# bitsyled-v1_2_1.net
KiCad netlist of a schematic drawn in EAGLE
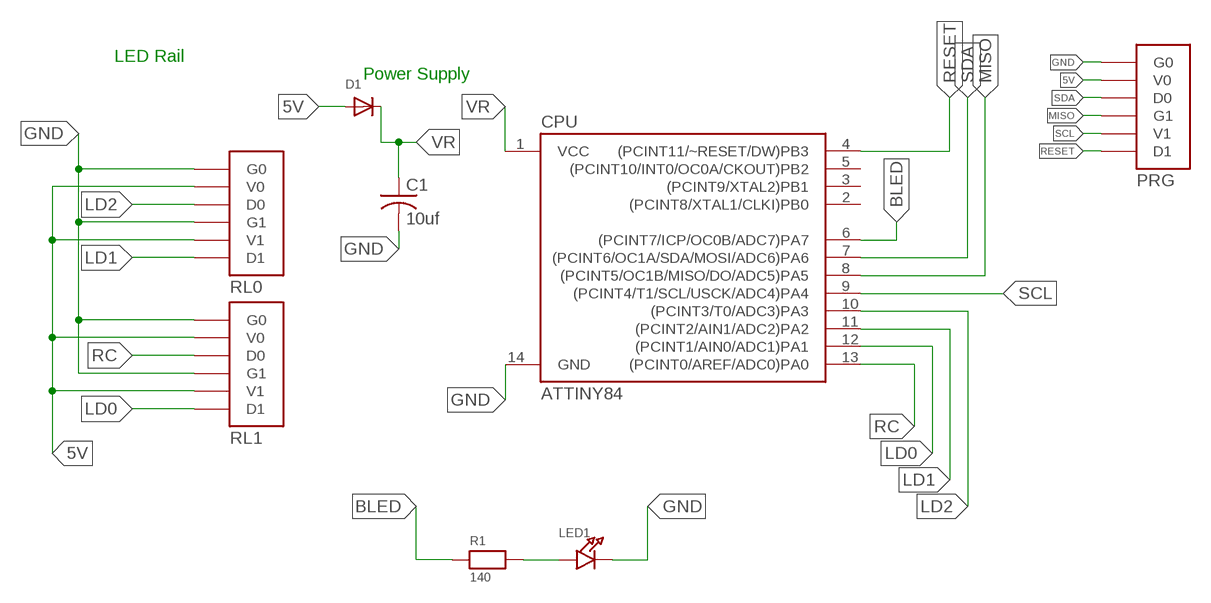
[diagram p0: schematic, sheet 1]

(export (version "E")
  (design (tool "Eeschema 10.0.6"))
  (components
    (comp (ref "C1")
      (value "10uf")
      (footprint "eagle-import:C0805")
      (libsource (lib "eagle-import") (part "C-USC0805"))
    )
    (comp (ref "CPU")
      (value "ATTINY84")
      (footprint "eagle-import:SO14")
      (libsource (lib "eagle-import") (part "ATTINY84"))
    )
    (comp (ref "D1")
      (value "DIODESOD-123")
      (footprint "eagle-import:SOD-123")
      (libsource (lib "eagle-import") (part "DIODESOD-123"))
    )
    (comp (ref "LED1")
      (value "LED0805_NOOUTLINE")
      (footprint "eagle-import:CHIPLED_0805_NOOUTLINE")
      (libsource (lib "eagle-import") (part "LED0805_NOOUTLINE"))
    )
    (comp (ref "PRG")
      (value "BITSYLED_1X6_RAILPRG")
      (footprint "eagle-import:BITSYLED_1X6_RAIL_PRG")
      (libsource (lib "eagle-import") (part "BITSYLED_1X6_RAILPRG"))
    )
    (comp (ref "R1")
      (value "140")
      (footprint "eagle-import:_0805")
      (libsource (lib "eagle-import") (part "RESISTOR_0805"))
    )
    (comp (ref "RL0")
      (value "BITSYLED_1X6_RAILNORMAL")
      (footprint "eagle-import:BITSYLED_1X6_RAIL")
      (libsource (lib "eagle-import") (part "BITSYLED_1X6_RAILNORMAL"))
    )
    (comp (ref "RL1")
      (value "BITSYLED_1X6_RAILREVERSED")
      (footprint "eagle-import:BITSYLED_1X6_RAIL_R")
      (libsource (lib "eagle-import") (part "BITSYLED_1X6_RAILREVERSED"))
    )
  )
  (nets
    (net (code "1") (name "5V") (class "Default")
      (node (ref "D1") (pin "A") (pinfunction "A_A") (pintype "passive"))
      (node (ref "PRG") (pin "V0") (pinfunction "V0_V0") (pintype "input"))
      (node (ref "RL0") (pin "V0") (pinfunction "V0_V0") (pintype "input"))
      (node (ref "RL0") (pin "V1") (pinfunction "V1_V1") (pintype "input"))
      (node (ref "RL1") (pin "V0") (pinfunction "V0_V0") (pintype "input"))
      (node (ref "RL1") (pin "V1") (pinfunction "V1_V1") (pintype "input"))
    )
    (net (code "2") (name "BLED") (class "Default")
      (node (ref "CPU") (pin "6") (pinfunction "(PCINT7/ICP/OC0B/ADC7)PA7_6") (pintype "bidirectional"))
      (node (ref "R1") (pin "1") (pinfunction "1_1") (pintype "passive"))
    )
    (net (code "3") (name "GND") (class "Default")
      (node (ref "C1") (pin "2") (pinfunction "2_2") (pintype "passive"))
      (node (ref "CPU") (pin "14") (pinfunction "GND_14") (pintype "bidirectional"))
      (node (ref "LED1") (pin "C") (pinfunction "C_C") (pintype "passive"))
      (node (ref "PRG") (pin "G0") (pinfunction "G0_G0") (pintype "input"))
      (node (ref "RL0") (pin "G0") (pinfunction "G0_G0") (pintype "input"))
      (node (ref "RL0") (pin "G1") (pinfunction "G1_G1") (pintype "input"))
      (node (ref "RL1") (pin "G0") (pinfunction "G0_G0") (pintype "input"))
      (node (ref "RL1") (pin "G1") (pinfunction "G1_G1") (pintype "input"))
    )
    (net (code "4") (name "LD0") (class "Default")
      (node (ref "CPU") (pin "12") (pinfunction "(PCINT1/AIN0/ADC1)PA1_12") (pintype "bidirectional"))
      (node (ref "RL1") (pin "D1") (pinfunction "D1_D1") (pintype "bidirectional"))
    )
    (net (code "5") (name "LD1") (class "Default")
      (node (ref "CPU") (pin "11") (pinfunction "(PCINT2/AIN1/ADC2)PA2_11") (pintype "bidirectional"))
      (node (ref "RL0") (pin "D1") (pinfunction "D1_D1") (pintype "bidirectional"))
    )
    (net (code "6") (name "LD2") (class "Default")
      (node (ref "CPU") (pin "10") (pinfunction "(PCINT3/T0/ADC3)PA3_10") (pintype "bidirectional"))
      (node (ref "RL0") (pin "D0") (pinfunction "D0_D0") (pintype "bidirectional"))
    )
    (net (code "7") (name "MISO") (class "Default")
      (node (ref "CPU") (pin "8") (pinfunction "(PCINT5/OC1B/MISO/DO/ADC5)PA5_8") (pintype "bidirectional"))
      (node (ref "PRG") (pin "G1") (pinfunction "G1_G1") (pintype "input"))
    )
    (net (code "8") (name "Net-(LED1-PadA)") (class "Default")
      (node (ref "LED1") (pin "A") (pinfunction "A_A") (pintype "passive"))
      (node (ref "R1") (pin "2") (pinfunction "2_2") (pintype "passive"))
    )
    (net (code "9") (name "RC") (class "Default")
      (node (ref "CPU") (pin "13") (pinfunction "(PCINT0/AREF/ADC0)PA0_13") (pintype "bidirectional"))
      (node (ref "RL1") (pin "D0") (pinfunction "D0_D0") (pintype "bidirectional"))
    )
    (net (code "10") (name "RESET") (class "Default")
      (node (ref "CPU") (pin "4") (pinfunction "(PCINT11/~{RESET/DW})PB3_4") (pintype "bidirectional"))
      (node (ref "PRG") (pin "D1") (pinfunction "D1_D1") (pintype "bidirectional"))
    )
    (net (code "11") (name "SCL") (class "Default")
      (node (ref "CPU") (pin "9") (pinfunction "(PCINT4/T1/SCL/USCK/ADC4)PA4_9") (pintype "bidirectional"))
      (node (ref "PRG") (pin "V1") (pinfunction "V1_V1") (pintype "input"))
    )
    (net (code "12") (name "SDA") (class "Default")
      (node (ref "CPU") (pin "7") (pinfunction "(PCINT6/OC1A/SDA/MOSI/ADC6)PA6_7") (pintype "bidirectional"))
      (node (ref "PRG") (pin "D0") (pinfunction "D0_D0") (pintype "bidirectional"))
    )
    (net (code "13") (name "VR") (class "Default")
      (node (ref "C1") (pin "1") (pinfunction "1_1") (pintype "passive"))
      (node (ref "CPU") (pin "1") (pinfunction "VCC_1") (pintype "bidirectional"))
      (node (ref "D1") (pin "C") (pinfunction "C_C") (pintype "passive"))
    )
    (net (code "14") (name "unconnected-(CPU-(PCINT8{slash}XTAL1{slash}CLKI)PB0-Pad2)") (class "Default")
      (node (ref "CPU") (pin "2") (pinfunction "(PCINT8/XTAL1/CLKI)PB0_2") (pintype "bidirectional"))
    )
    (net (code "15") (name "unconnected-(CPU-(PCINT9{slash}XTAL2)PB1-Pad3)") (class "Default")
      (node (ref "CPU") (pin "3") (pinfunction "(PCINT9/XTAL2)PB1_3") (pintype "bidirectional"))
    )
    (net (code "16") (name "unconnected-(CPU-(PCINT10{slash}INT0{slash}OC0A{slash}CKOUT)PB2-Pad5)") (class "Default")
      (node (ref "CPU") (pin "5") (pinfunction "(PCINT10/INT0/OC0A/CKOUT)PB2_5") (pintype "bidirectional"))
    )
  )
)
